# ai_breakout_ws2812b.net
KiCad netlist of a schematic drawn in EAGLE
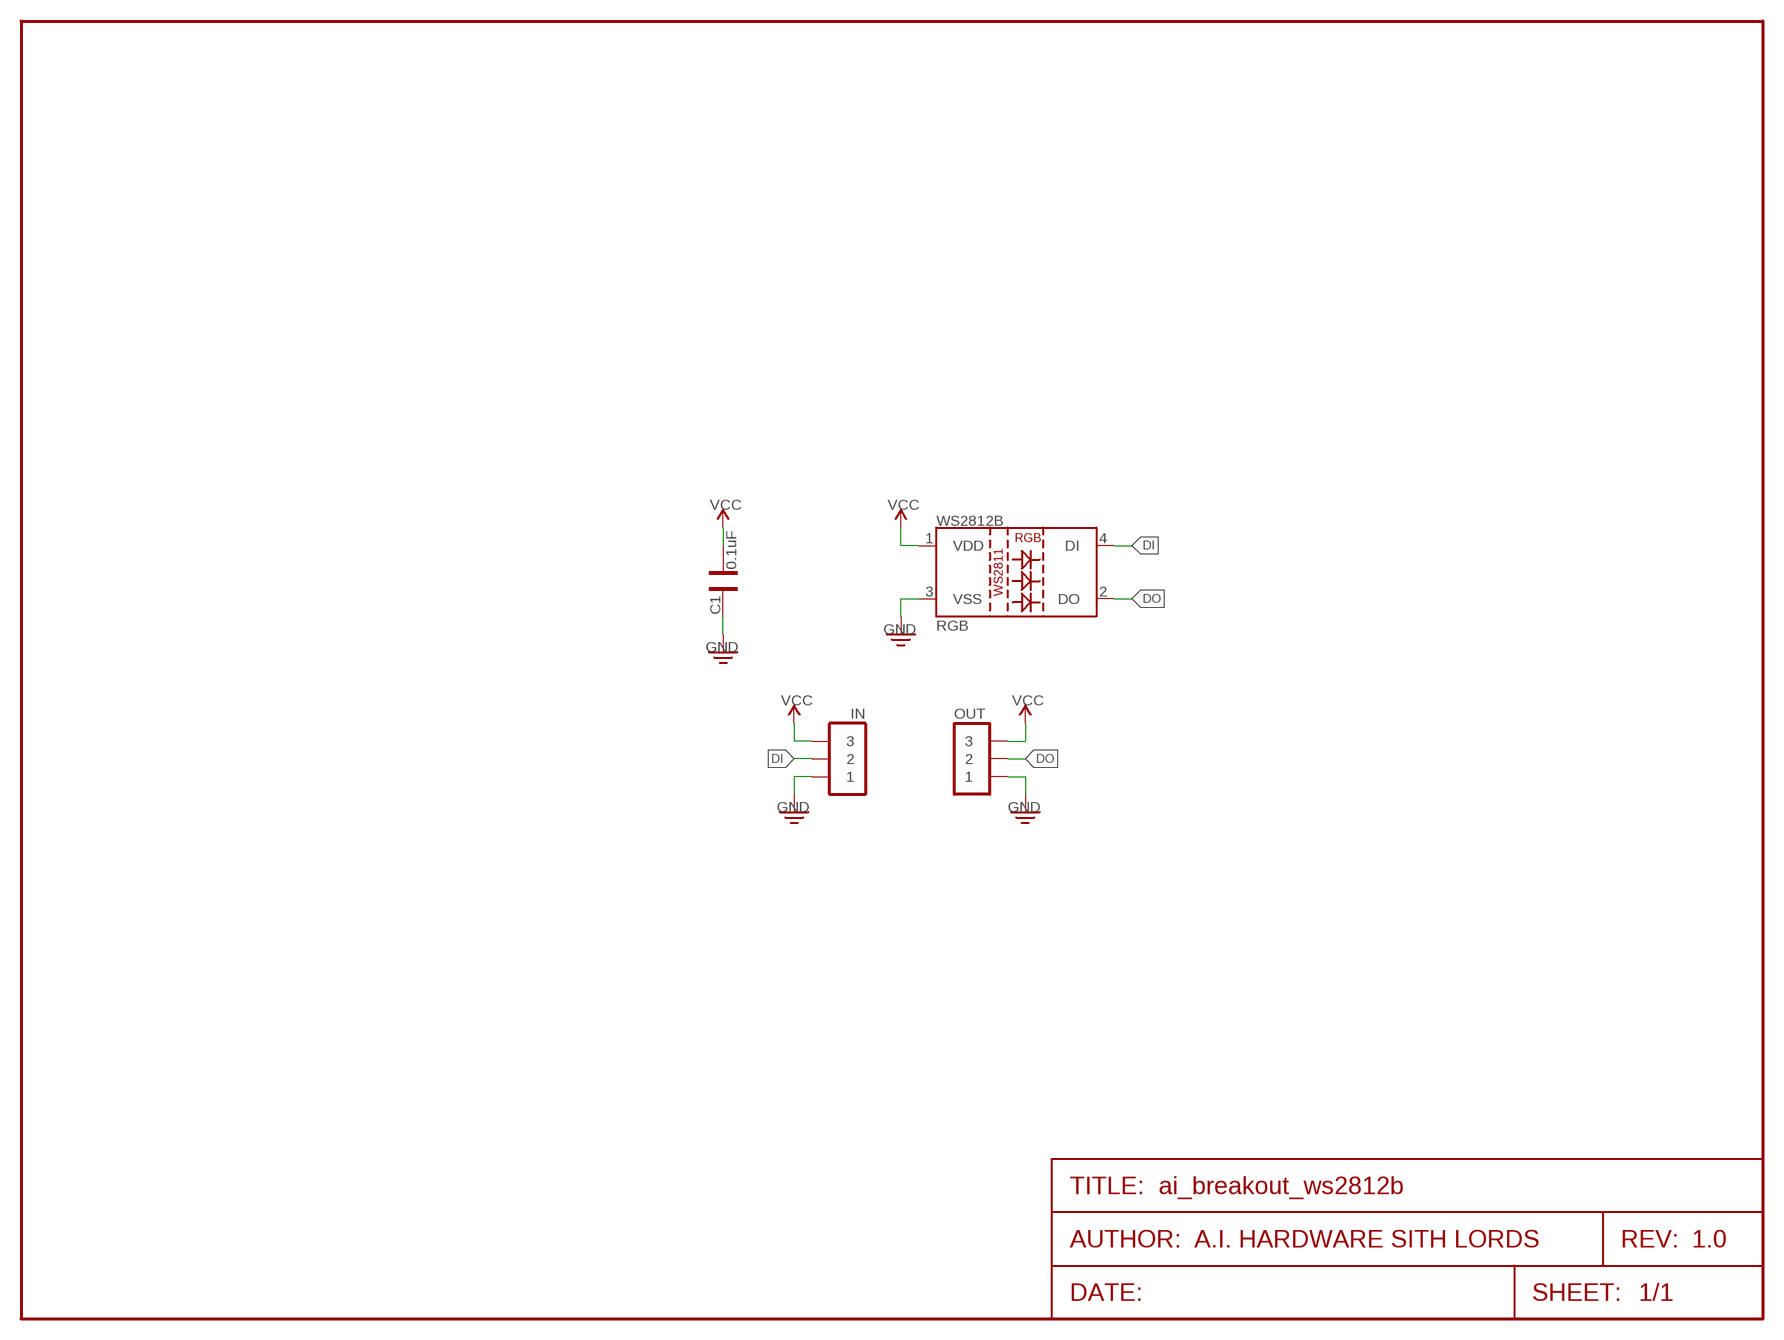
[diagram p0: schematic, sheet 1]

(export (version "E")
  (design (tool "Eeschema 10.0.6"))
  (components
    (comp (ref "C1")
      (value "0.1uF")
      (footprint "eagle-import:CAP-0402")
      (libsource (lib "eagle-import") (part "CAP0402"))
    )
    (comp (ref "IN")
      (value "1X03")
      (footprint "eagle-import:1X03")
      (libsource (lib "eagle-import") (part "1X03"))
    )
    (comp (ref "OUT")
      (value "1X03NOFIRST")
      (footprint "eagle-import:1X03-NOFIRST")
      (libsource (lib "eagle-import") (part "1X03NOFIRST"))
    )
    (comp (ref "RGB")
      (value "LED-WS2812B-SM")
      (footprint "eagle-import:LED-WS2812B-SM")
      (libsource (lib "eagle-import") (part "LED-WS2812B-SM"))
    )
  )
  (nets
    (net (code "1") (name "DI") (class "Default")
      (node (ref "IN") (pin "2") (pinfunction "2_2") (pintype "bidirectional"))
      (node (ref "RGB") (pin "4") (pinfunction "DI_4") (pintype "bidirectional"))
    )
    (net (code "2") (name "DO") (class "Default")
      (node (ref "OUT") (pin "2") (pinfunction "2_2") (pintype "bidirectional"))
      (node (ref "RGB") (pin "2") (pinfunction "DO_2") (pintype "bidirectional"))
    )
    (net (code "3") (name "GND") (class "Default")
      (node (ref "C1") (pin "2") (pinfunction "2_2") (pintype "passive"))
      (node (ref "IN") (pin "1") (pinfunction "1_1") (pintype "bidirectional"))
      (node (ref "OUT") (pin "1") (pinfunction "1_1") (pintype "bidirectional"))
      (node (ref "RGB") (pin "3") (pinfunction "VSS_3") (pintype "bidirectional"))
    )
    (net (code "4") (name "VCC") (class "Default")
      (node (ref "C1") (pin "1") (pinfunction "1_1") (pintype "passive"))
      (node (ref "IN") (pin "3") (pinfunction "3_3") (pintype "bidirectional"))
      (node (ref "OUT") (pin "3") (pinfunction "3_3") (pintype "bidirectional"))
      (node (ref "RGB") (pin "1") (pinfunction "VDD_1") (pintype "bidirectional"))
    )
  )
)
